# s2m4x.net
KiCad netlist of a schematic drawn in Altium Designer
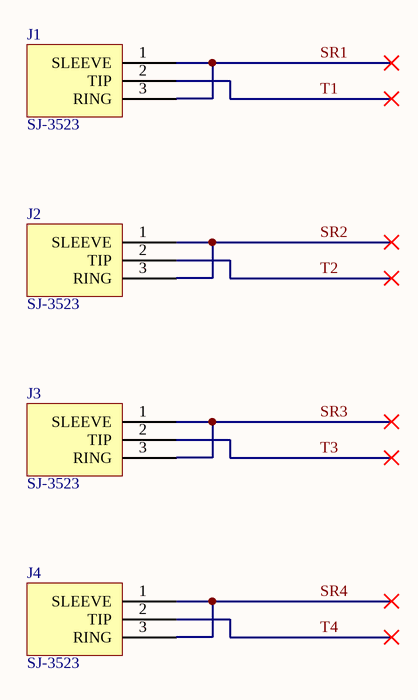
[diagram p0: s2m4x.SchDoc]

(export (version "E")
  (design (tool "Eeschema 10.0.6"))
  (components
    (comp (ref "J1")
      (value "SJ-3523")
      (footprint "SJ-352X")
      (libsource (lib "JF_master_lib") (part "SJ-3523"))
    )
    (comp (ref "J2")
      (value "SJ-3523")
      (footprint "SJ-352X")
      (libsource (lib "JF_master_lib") (part "SJ-3523"))
    )
    (comp (ref "J3")
      (value "SJ-3523")
      (footprint "SJ-352X")
      (libsource (lib "JF_master_lib") (part "SJ-3523"))
    )
    (comp (ref "J4")
      (value "SJ-3523")
      (footprint "SJ-352X")
      (libsource (lib "JF_master_lib") (part "SJ-3523"))
    )
  )
  (nets
    (net (code "1") (name "/SR1") (class "Default")
      (node (ref "J1") (pin "1") (pinfunction "SLEEVE_1") (pintype "passive"))
      (node (ref "J1") (pin "3") (pinfunction "RING_3") (pintype "passive"))
    )
    (net (code "2") (name "/SR2") (class "Default")
      (node (ref "J2") (pin "1") (pinfunction "SLEEVE_1") (pintype "passive"))
      (node (ref "J2") (pin "3") (pinfunction "RING_3") (pintype "passive"))
    )
    (net (code "3") (name "/SR3") (class "Default")
      (node (ref "J3") (pin "1") (pinfunction "SLEEVE_1") (pintype "passive"))
      (node (ref "J3") (pin "3") (pinfunction "RING_3") (pintype "passive"))
    )
    (net (code "4") (name "/SR4") (class "Default")
      (node (ref "J4") (pin "1") (pinfunction "SLEEVE_1") (pintype "passive"))
      (node (ref "J4") (pin "3") (pinfunction "RING_3") (pintype "passive"))
    )
    (net (code "5") (name "/T1") (class "Default")
      (node (ref "J1") (pin "2") (pinfunction "TIP_2") (pintype "passive+no_connect"))
    )
    (net (code "6") (name "/T2") (class "Default")
      (node (ref "J2") (pin "2") (pinfunction "TIP_2") (pintype "passive+no_connect"))
    )
    (net (code "7") (name "/T3") (class "Default")
      (node (ref "J3") (pin "2") (pinfunction "TIP_2") (pintype "passive+no_connect"))
    )
    (net (code "8") (name "/T4") (class "Default")
      (node (ref "J4") (pin "2") (pinfunction "TIP_2") (pintype "passive+no_connect"))
    )
  )
)
